# Data_Logger.net
KiCad netlist of a schematic drawn in Altium Designer
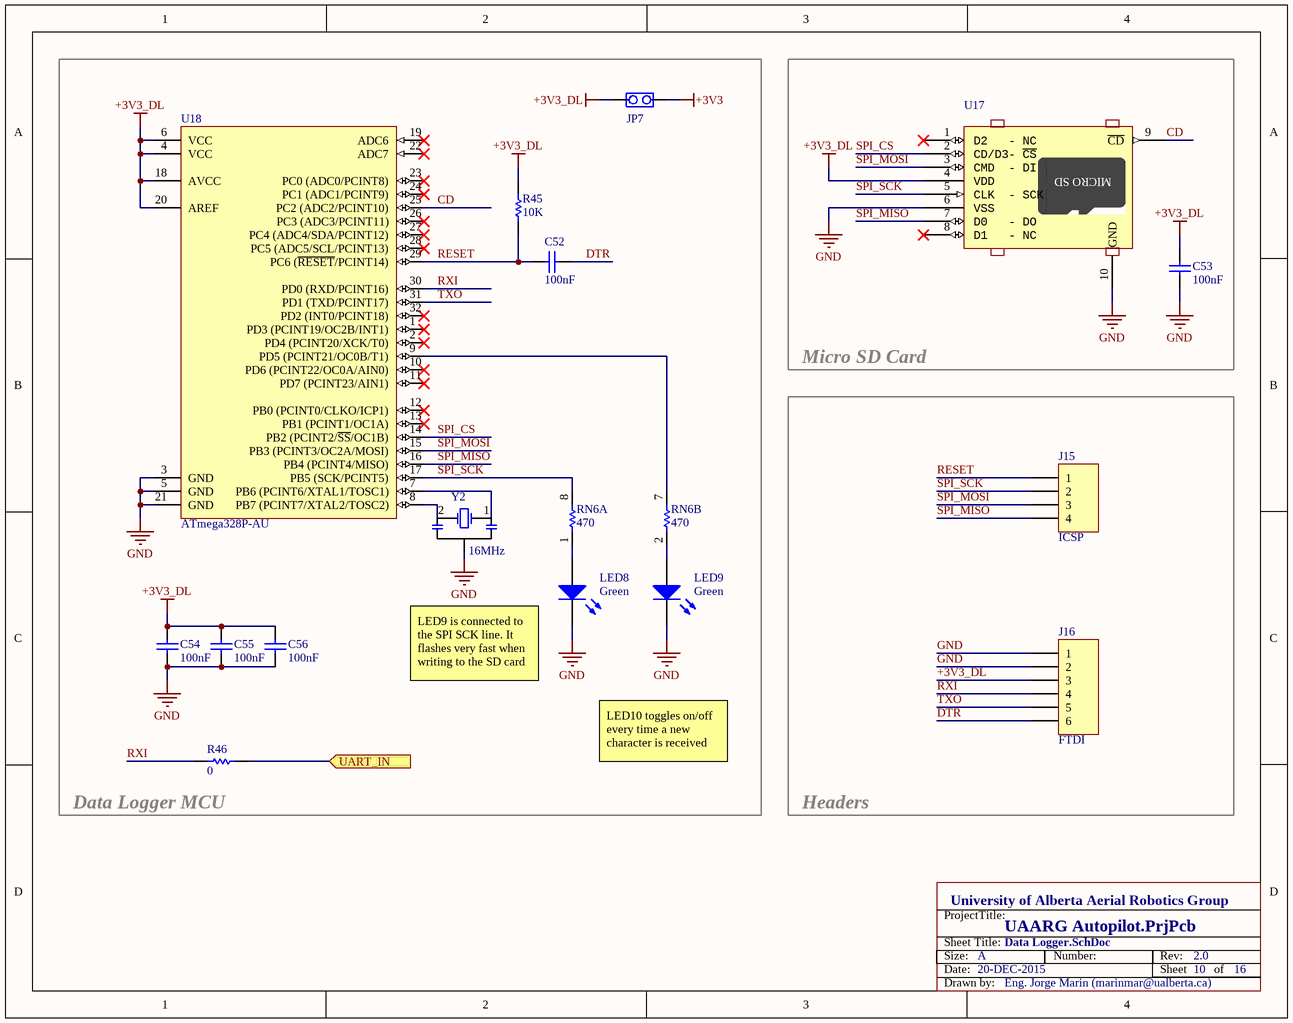
[diagram p0: Data Logger.SchDoc]

(export (version "E")
  (design (tool "Eeschema 10.0.6"))
  (components
    (comp (ref "C52")
      (value "100nF")
      (footprint "CAP_0402[1005M]")
      (description "CAP CER 0.1UF 10V 10% X7R 0402")
      (fields
        (field (name "MANUFACTURER") "Yageo")
        (field (name "MANUFACTURER PART NUMBER") "CC0402KRX7R6BB104")
      )
      (libsource (lib "UAARG Autopilot") (part "CAP"))
    )
    (comp (ref "C53")
      (value "100nF")
      (footprint "CAP_0402[1005M]")
      (description "CAP CER 0.1UF 10V 10% X7R 0402")
      (fields
        (field (name "MANUFACTURER") "Yageo")
        (field (name "MANUFACTURER PART NUMBER") "CC0402KRX7R6BB104")
      )
      (libsource (lib "UAARG Autopilot") (part "CAP"))
    )
    (comp (ref "C54")
      (value "100nF")
      (footprint "CAP_0402[1005M]")
      (description "CAP CER 0.1UF 10V 10% X7R 0402")
      (fields
        (field (name "MANUFACTURER") "Yageo")
        (field (name "MANUFACTURER PART NUMBER") "CC0402KRX7R6BB104")
      )
      (libsource (lib "UAARG Autopilot") (part "CAP"))
    )
    (comp (ref "C55")
      (value "100nF")
      (footprint "CAP_0402[1005M]")
      (description "CAP CER 0.1UF 10V 10% X7R 0402")
      (fields
        (field (name "MANUFACTURER") "Yageo")
        (field (name "MANUFACTURER PART NUMBER") "CC0402KRX7R6BB104")
      )
      (libsource (lib "UAARG Autopilot") (part "CAP"))
    )
    (comp (ref "C56")
      (value "100nF")
      (footprint "CAP_0402[1005M]")
      (description "CAP CER 0.1UF 10V 10% X7R 0402")
      (fields
        (field (name "MANUFACTURER") "Yageo")
        (field (name "MANUFACTURER PART NUMBER") "CC0402KRX7R6BB104")
      )
      (libsource (lib "UAARG Autopilot") (part "CAP"))
    )
    (comp (ref "J15")
      (value "ICSP")
      (footprint "1X04")
      (description "Header, 4-Pin")
      (libsource (lib "UAARG Autopilot") (part "Header 4"))
    )
    (comp (ref "J16")
      (value "FTDI")
      (footprint "HEADER RA 6 2.54")
      (description "Header, 6-Pin")
      (fields
        (field (name "MANUFACTURER PART NUMBER") "961106-5500-AR-PR")
        (field (name "MANUFACTURER") "3M")
      )
      (libsource (lib "Miscellaneous Connectors") (part "Header 6"))
    )
    (comp (ref "JP7")
      (value "Jumper")
      (footprint "HDR_1x02_JMP")
      (libsource (lib "UAARG Autopilot") (part "Jumper"))
    )
    (comp (ref "LED8")
      (value "LED")
      (footprint "LED_0603[1608M]")
      (description "LED GREEN CLEAR 0603 SMD")
      (fields
        (field (name "MANUFACTURER") "Lite-On Inc.")
        (field (name "MANUFACTURER PART NUMBER") "LTST-C190KGKT")
        (field (name "COLOR") "Green")
      )
      (libsource (lib "UAARG Autopilot") (part "LED"))
    )
    (comp (ref "LED9")
      (value "LED")
      (footprint "LED_0603[1608M]")
      (description "LED GREEN CLEAR 0603 SMD")
      (fields
        (field (name "MANUFACTURER") "Lite-On Inc.")
        (field (name "MANUFACTURER PART NUMBER") "LTST-C190KGKT")
        (field (name "COLOR") "Green")
      )
      (libsource (lib "UAARG Autopilot") (part "LED"))
    )
    (comp (ref "R45")
      (value "10K")
      (footprint "RES_0402[1005M]")
      (description "Resistor")
      (fields
        (field (name "MANUFACTURER") "Yageo")
        (field (name "MANUFACTURER PART NUMBER") "RC0402FR-0710KL")
      )
      (libsource (lib "UAARG Autopilot") (part "RES"))
    )
    (comp (ref "R46")
      (value "0")
      (footprint "JUMPER_RES_0402")
      (description "Resistor")
      (fields
        (field (name "MANUFACTURER PART NUMBER") "RC0402JR-070RL")
        (field (name "MANUFACTURER") "Yageo")
      )
      (libsource (lib "UAARG Autopilot") (part "RES"))
    )
    (comp (ref "RN6")
      (value "470")
      (footprint "RES ARRAY SMD")
      (description "Isolated Resistor Network")
      (fields
        (field (name "MANUFACTURER") "Yageo")
        (field (name "MANUFACTURER PART NUMBER") "YC164-JR-07470RL")
      )
      (libsource (lib "UAARG Autopilot") (part "Res Network 1"))
    )
    (comp (ref "U17")
      (value "MICRO-SD_1")
      (footprint "MICRO-SD_1")
      (description "GCT MEM2051-00-195-00-A")
      (fields
        (field (name "MANUFACTURER") "GLOBAL CONNECTOR TECHNOLOGY")
        (field (name "MANUFACTURER PART NUMBER") "MEM2051-00-195-00-A")
      )
      (libsource (lib "UAARG Autopilot") (part "MICRO-SD_1"))
    )
    (comp (ref "U18")
      (value "ATmega328P-AU")
      (footprint "TQFP32A_M")
      (fields (field (name "MANUFACTURER") "Atmel") (field (name "MANUFACTURER PART NUMBER") "ATMEGA328P-AU"))
      (libsource (lib "Atmel Microcontroller 8-Bit megaAVR") (part "ATmega328P-AU"))
    )
    (comp (ref "Y2")
      (value "XTAL_3")
      (footprint "RESONATOR_3213")
      (description "Resonator with built in capacitors")
      (fields
        (field (name "FREQUENCY") "16MHz")
        (field (name "MANUFACTURER PART NUMBER") "CSTCE16M0V53-R0")
        (field (name "MANUFACTURER") "Murata Electronics North America")
      )
      (libsource (lib "UAARG Autopilot") (part "XTAL_3"))
    )
  )
  (nets
    (net (code "1") (name "+3V3") (class "Default")
      (node (ref "JP7") (pin "2") (pinfunction "2_2") (pintype "passive"))
    )
    (net (code "2") (name "+3V3_DL") (class "Default")
      (node (ref "C53") (pin "1") (pinfunction "1_1") (pintype "passive"))
      (node (ref "C54") (pin "1") (pinfunction "1_1") (pintype "passive"))
      (node (ref "C55") (pin "1") (pinfunction "1_1") (pintype "passive"))
      (node (ref "C56") (pin "1") (pinfunction "1_1") (pintype "passive"))
      (node (ref "J16") (pin "3") (pinfunction "3_3") (pintype "passive"))
      (node (ref "JP7") (pin "1") (pinfunction "1_1") (pintype "passive"))
      (node (ref "R45") (pin "2") (pinfunction "2_2") (pintype "passive"))
      (node (ref "U17") (pin "4") (pinfunction "VDD_4") (pintype "power_in"))
      (node (ref "U18") (pin "18") (pinfunction "AVCC_18") (pintype "power_in"))
      (node (ref "U18") (pin "20") (pinfunction "AREF_20") (pintype "passive"))
      (node (ref "U18") (pin "4") (pinfunction "VCC_4") (pintype "power_in"))
      (node (ref "U18") (pin "6") (pinfunction "VCC_6") (pintype "power_in"))
    )
    (net (code "3") (name "/CD") (class "Default")
      (node (ref "U17") (pin "9") (pinfunction "~{CD}_9") (pintype "output"))
      (node (ref "U18") (pin "25") (pinfunction "PC2_(ADC2/PCINT10)_25") (pintype "bidirectional"))
    )
    (net (code "4") (name "/DTR") (class "Default")
      (node (ref "C52") (pin "2") (pinfunction "2_2") (pintype "passive"))
      (node (ref "J16") (pin "6") (pinfunction "6_6") (pintype "passive"))
    )
    (net (code "5") (name "/RESET") (class "Default")
      (node (ref "C52") (pin "1") (pinfunction "1_1") (pintype "passive"))
      (node (ref "J15") (pin "1") (pinfunction "1_1") (pintype "passive"))
      (node (ref "R45") (pin "1") (pinfunction "1_1") (pintype "passive"))
      (node (ref "U18") (pin "29") (pinfunction "PC6_(~{RESET}/PCINT14)_29") (pintype "bidirectional"))
    )
    (net (code "6") (name "/RXI") (class "Default")
      (node (ref "J16") (pin "4") (pinfunction "4_4") (pintype "passive"))
      (node (ref "R46") (pin "2") (pinfunction "2_2") (pintype "passive"))
      (node (ref "U18") (pin "30") (pinfunction "PD0_(RXD/PCINT16)_30") (pintype "bidirectional"))
    )
    (net (code "7") (name "/SPI_CS") (class "Default")
      (node (ref "U17") (pin "2") (pinfunction "CD/D3-_~{CS}_2") (pintype "bidirectional"))
      (node (ref "U18") (pin "14") (pinfunction "PB2_(PCINT2/~{SS}/OC1B)_14") (pintype "bidirectional"))
    )
    (net (code "8") (name "/SPI_MISO") (class "Default")
      (node (ref "J15") (pin "4") (pinfunction "4_4") (pintype "passive"))
      (node (ref "U17") (pin "7") (pinfunction "D0___-_DO_7") (pintype "bidirectional"))
      (node (ref "U18") (pin "16") (pinfunction "PB4_(PCINT4/MISO)_16") (pintype "bidirectional"))
    )
    (net (code "9") (name "/SPI_MOSI") (class "Default")
      (node (ref "J15") (pin "3") (pinfunction "3_3") (pintype "passive"))
      (node (ref "U17") (pin "3") (pinfunction "CMD__-_DI_3") (pintype "bidirectional"))
      (node (ref "U18") (pin "15") (pinfunction "PB3_(PCINT3/OC2A/MOSI)_15") (pintype "bidirectional"))
    )
    (net (code "10") (name "/SPI_SCK") (class "Default")
      (node (ref "J15") (pin "2") (pinfunction "2_2") (pintype "passive"))
      (node (ref "RN6") (pin "8") (pinfunction "8_8") (pintype "passive"))
      (node (ref "U17") (pin "5") (pinfunction "CLK__-_SCK_5") (pintype "input"))
      (node (ref "U18") (pin "17") (pinfunction "PB5_(SCK/PCINT5)_17") (pintype "bidirectional"))
    )
    (net (code "11") (name "/TXO") (class "Default")
      (node (ref "J16") (pin "5") (pinfunction "5_5") (pintype "passive"))
      (node (ref "U18") (pin "31") (pinfunction "PD1_(TXD/PCINT17)_31") (pintype "bidirectional"))
    )
    (net (code "12") (name "/UART_IN") (class "Default")
      (node (ref "R46") (pin "1") (pinfunction "1_1") (pintype "passive"))
    )
    (net (code "13") (name "GND") (class "Default")
      (node (ref "C53") (pin "2") (pinfunction "2_2") (pintype "passive"))
      (node (ref "C54") (pin "2") (pinfunction "2_2") (pintype "passive"))
      (node (ref "C55") (pin "2") (pinfunction "2_2") (pintype "passive"))
      (node (ref "C56") (pin "2") (pinfunction "2_2") (pintype "passive"))
      (node (ref "J16") (pin "1") (pinfunction "1_1") (pintype "passive"))
      (node (ref "J16") (pin "2") (pinfunction "2_2") (pintype "passive"))
      (node (ref "LED8") (pin "2") (pinfunction "K_2") (pintype "passive"))
      (node (ref "LED9") (pin "2") (pinfunction "K_2") (pintype "passive"))
      (node (ref "U17") (pin "10") (pinfunction "GND_10") (pintype "power_in"))
      (node (ref "U17") (pin "6") (pinfunction "VSS_6") (pintype "power_in"))
      (node (ref "U18") (pin "21") (pinfunction "GND_21") (pintype "power_in"))
      (node (ref "U18") (pin "3") (pinfunction "GND_3") (pintype "power_in"))
      (node (ref "U18") (pin "5") (pinfunction "GND_5") (pintype "power_in"))
      (node (ref "Y2") (pin "3") (pinfunction "GND_3") (pintype "passive"))
    )
    (net (code "14") (name "Net-(LED8-A)") (class "Default")
      (node (ref "LED8") (pin "1") (pinfunction "A_1") (pintype "passive"))
      (node (ref "RN6") (pin "1") (pinfunction "1_1") (pintype "passive"))
    )
    (net (code "15") (name "Net-(LED9-A)") (class "Default")
      (node (ref "LED9") (pin "1") (pinfunction "A_1") (pintype "passive"))
      (node (ref "RN6") (pin "2") (pinfunction "2_2") (pintype "passive"))
    )
    (net (code "16") (name "Net-(U18-PB6_(PCINT6{slash}XTAL1{slash}TOSC1))") (class "Default")
      (node (ref "U18") (pin "7") (pinfunction "PB6_(PCINT6/XTAL1/TOSC1)_7") (pintype "bidirectional"))
      (node (ref "Y2") (pin "1") (pinfunction "OSC1_1") (pintype "passive"))
    )
    (net (code "17") (name "Net-(U18-PB7_(PCINT7{slash}XTAL2{slash}TOSC2))") (class "Default")
      (node (ref "U18") (pin "8") (pinfunction "PB7_(PCINT7/XTAL2/TOSC2)_8") (pintype "bidirectional"))
      (node (ref "Y2") (pin "2") (pinfunction "OSC2_2") (pintype "passive"))
    )
    (net (code "18") (name "Net-(U18-PD5_(PCINT21{slash}OC0B{slash}T1))") (class "Default")
      (node (ref "RN6") (pin "7") (pinfunction "7_7") (pintype "passive"))
      (node (ref "U18") (pin "9") (pinfunction "PD5_(PCINT21/OC0B/T1)_9") (pintype "bidirectional"))
    )
    (net (code "19") (name "unconnected-(U17-D1___-_NC-Pad8)") (class "Default")
      (node (ref "U17") (pin "8") (pinfunction "D1___-_NC_8") (pintype "bidirectional+no_connect"))
    )
    (net (code "20") (name "unconnected-(U17-D2___-_NC-Pad1)") (class "Default")
      (node (ref "U17") (pin "1") (pinfunction "D2___-_NC_1") (pintype "bidirectional+no_connect"))
    )
    (net (code "21") (name "unconnected-(U18-ADC6-Pad19)") (class "Default")
      (node (ref "U18") (pin "19") (pinfunction "ADC6_19") (pintype "input+no_connect"))
    )
    (net (code "22") (name "unconnected-(U18-ADC7-Pad22)") (class "Default")
      (node (ref "U18") (pin "22") (pinfunction "ADC7_22") (pintype "input+no_connect"))
    )
    (net (code "23") (name "unconnected-(U18-PB0_(PCINT0{slash}CLKO{slash}ICP1)-Pad12)") (class "Default")
      (node (ref "U18") (pin "12") (pinfunction "PB0_(PCINT0/CLKO/ICP1)_12") (pintype "bidirectional+no_connect"))
    )
    (net (code "24") (name "unconnected-(U18-PB1_(PCINT1{slash}OC1A)-Pad13)") (class "Default")
      (node (ref "U18") (pin "13") (pinfunction "PB1_(PCINT1/OC1A)_13") (pintype "bidirectional+no_connect"))
    )
    (net (code "25") (name "unconnected-(U18-PC0_(ADC0{slash}PCINT8)-Pad23)") (class "Default")
      (node (ref "U18") (pin "23") (pinfunction "PC0_(ADC0/PCINT8)_23") (pintype "bidirectional+no_connect"))
    )
    (net (code "26") (name "unconnected-(U18-PC1_(ADC1{slash}PCINT9)-Pad24)") (class "Default")
      (node (ref "U18") (pin "24") (pinfunction "PC1_(ADC1/PCINT9)_24") (pintype "bidirectional+no_connect"))
    )
    (net (code "27") (name "unconnected-(U18-PC3_(ADC3{slash}PCINT11)-Pad26)") (class "Default")
      (node (ref "U18") (pin "26") (pinfunction "PC3_(ADC3/PCINT11)_26") (pintype "bidirectional+no_connect"))
    )
    (net (code "28") (name "unconnected-(U18-PC4_(ADC4{slash}SDA{slash}PCINT12)-Pad27)") (class "Default")
      (node (ref "U18") (pin "27") (pinfunction "PC4_(ADC4/SDA/PCINT12)_27") (pintype "bidirectional+no_connect"))
    )
    (net (code "29") (name "unconnected-(U18-PC5_(ADC5{slash}SCL{slash}PCINT13)-Pad28)") (class "Default")
      (node (ref "U18") (pin "28") (pinfunction "PC5_(ADC5/SCL/PCINT13)_28") (pintype "bidirectional+no_connect"))
    )
    (net (code "30") (name "unconnected-(U18-PD2_(INT0{slash}PCINT18)-Pad32)") (class "Default")
      (node (ref "U18") (pin "32") (pinfunction "PD2_(INT0/PCINT18)_32") (pintype "bidirectional+no_connect"))
    )
    (net (code "31") (name "unconnected-(U18-PD3_(PCINT19{slash}OC2B{slash}INT1)-Pad1)") (class "Default")
      (node (ref "U18") (pin "1") (pinfunction "PD3_(PCINT19/OC2B/INT1)_1") (pintype "bidirectional+no_connect"))
    )
    (net (code "32") (name "unconnected-(U18-PD4_(PCINT20{slash}XCK{slash}T0)-Pad2)") (class "Default")
      (node (ref "U18") (pin "2") (pinfunction "PD4_(PCINT20/XCK/T0)_2") (pintype "bidirectional+no_connect"))
    )
    (net (code "33") (name "unconnected-(U18-PD6_(PCINT22{slash}OC0A{slash}AIN0)-Pad10)") (class "Default")
      (node (ref "U18") (pin "10") (pinfunction "PD6_(PCINT22/OC0A/AIN0)_10") (pintype "bidirectional+no_connect"))
    )
    (net (code "34") (name "unconnected-(U18-PD7_(PCINT23{slash}AIN1)-Pad11)") (class "Default")
      (node (ref "U18") (pin "11") (pinfunction "PD7_(PCINT23/AIN1)_11") (pintype "bidirectional+no_connect"))
    )
  )
)
